# POWER_NODE.net
KiCad netlist of a schematic drawn in Altium Designer
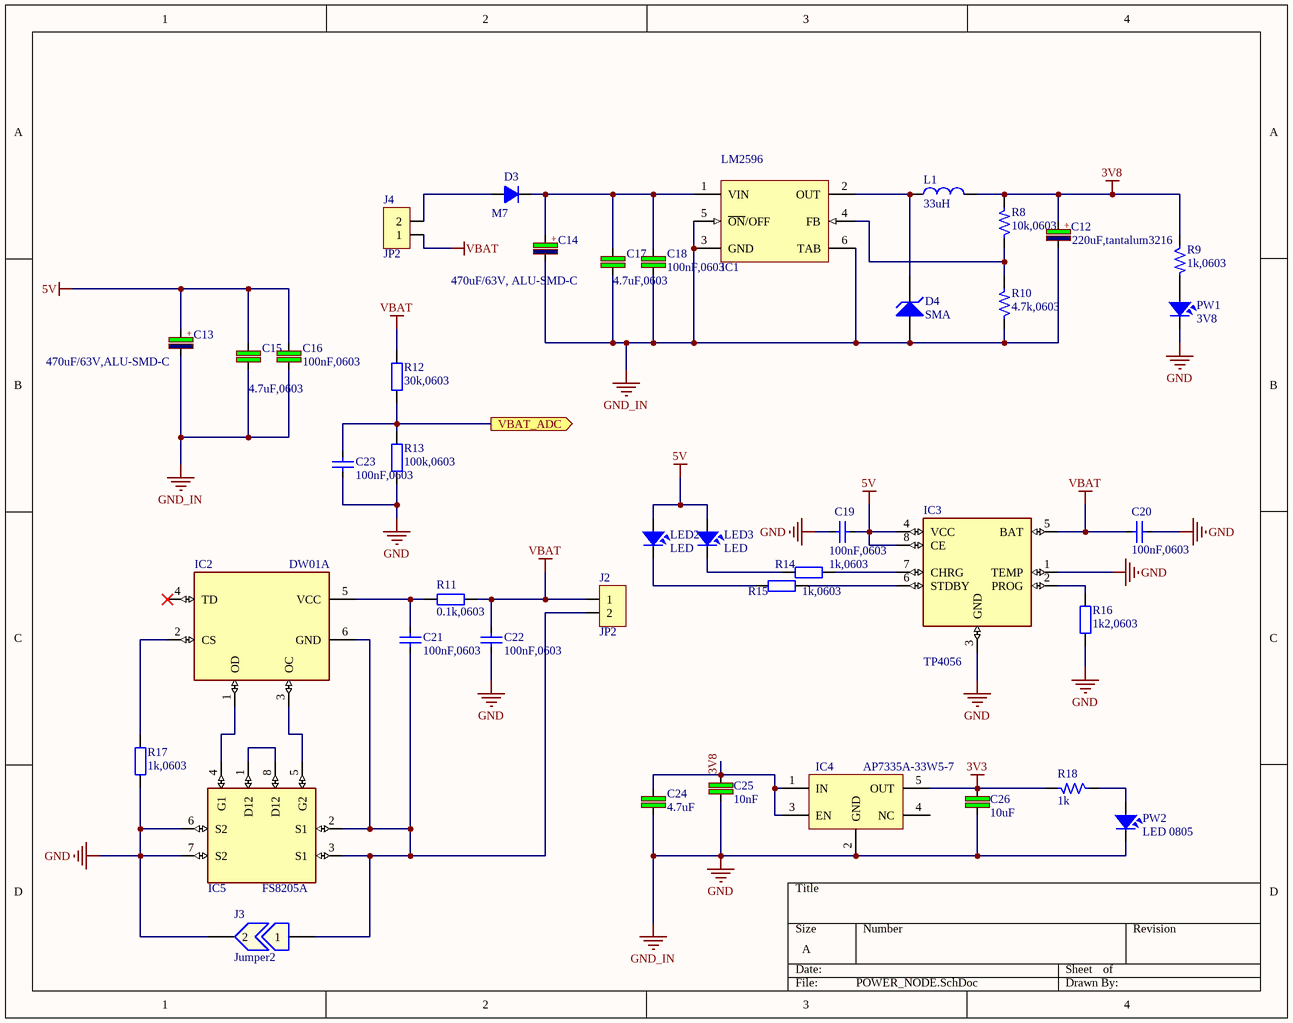
[diagram p0: POWER_NODE.SchDoc]

(export (version "E")
  (design (tool "Eeschema 10.0.6"))
  (components
    (comp (ref "C12")
      (value "220uF,tantalum3216")
      (footprint "CAP_TANTALUM_3216")
      (description "220µF Molded Tantalum Polymer Capacitor 16V 2917 (7343 Metric) 40mOhm @ 100kHz")
      (fields
        (field (name "MANUFACTURER") "AVX Corporation")
        (field (name "PART NUMBER") "TCME227M016R0040E")
      )
      (libsource (lib "Anh_Trung") (part "CP5"))
    )
    (comp (ref "C13")
      (value "470uF/63V,ALU-SMD-C")
      (footprint "CAP-ALU-SMD-C")
      (description "Cap 470uF/63V")
      (libsource (lib "Main") (part "CP3"))
    )
    (comp (ref "C14")
      (value "470uF/63V, ALU-SMD-C")
      (footprint "CAP-ALU-SMD-C")
      (description "Cap 470uF/63V")
      (libsource (lib "Main") (part "CP3"))
    )
    (comp (ref "C15")
      (value "4.7uF,0603")
      (footprint "CAP_0603")
      (description "4.7µF ±10% 35V Ceramic Capacitor X5R 0805 (2012 Metric)")
      (fields
        (field (name "MANUFACTURER") "Samsung Electro-Mechanics")
        (field (name "PART NUMBER") "CL21A475KLCLQNC")
      )
      (libsource (lib "Anh_Trung") (part "C"))
    )
    (comp (ref "C16")
      (value "100nF,0603")
      (footprint "CAP_0603")
      (description "4.7µF ±10% 35V Ceramic Capacitor X5R 0805 (2012 Metric)")
      (fields
        (field (name "MANUFACTURER") "Samsung Electro-Mechanics")
        (field (name "PART NUMBER") "CL21A475KLCLQNC")
      )
      (libsource (lib "Anh_Trung") (part "C"))
    )
    (comp (ref "C17")
      (value "4.7uF,0603")
      (footprint "CAP_0603")
      (description "4.7µF ±10% 35V Ceramic Capacitor X5R 0805 (2012 Metric)")
      (fields
        (field (name "MANUFACTURER") "Samsung Electro-Mechanics")
        (field (name "PART NUMBER") "CL21A475KLCLQNC")
      )
      (libsource (lib "Anh_Trung") (part "C"))
    )
    (comp (ref "C18")
      (value "100nF,0603")
      (footprint "CAP_0603")
      (description "4.7µF ±10% 35V Ceramic Capacitor X5R 0805 (2012 Metric)")
      (fields
        (field (name "MANUFACTURER") "Samsung Electro-Mechanics")
        (field (name "PART NUMBER") "CL21A475KLCLQNC")
      )
      (libsource (lib "Anh_Trung") (part "C"))
    )
    (comp (ref "C19")
      (value "100nF,0603")
      (footprint "CAP_0603")
      (description "Capacitor")
      (fields (field (name "PUBLISHER") "Altium Limited"))
      (libsource (lib "My Library") (part "CapSMD"))
    )
    (comp (ref "C20")
      (value "100nF,0603")
      (footprint "CAP_0603")
      (description "Capacitor")
      (fields (field (name "PUBLISHER") "Altium Limited"))
      (libsource (lib "My Library") (part "CapSMD"))
    )
    (comp (ref "C21")
      (value "100nF,0603")
      (footprint "CAP_0603")
      (description "Capacitor")
      (fields (field (name "PUBLISHER") "Altium Limited"))
      (libsource (lib "My Library") (part "CapSMD"))
    )
    (comp (ref "C22")
      (value "100nF,0603")
      (footprint "CAP_0603")
      (description "Capacitor")
      (fields (field (name "PUBLISHER") "Altium Limited"))
      (libsource (lib "My Library") (part "CapSMD"))
    )
    (comp (ref "C23")
      (value "100nF,0603")
      (footprint "CAP_0603")
      (description "Capacitor")
      (fields (field (name "PUBLISHER") "Altium Limited"))
      (libsource (lib "My Library") (part "CapSMD"))
    )
    (comp (ref "C24")
      (value "4.7uF")
      (footprint "CAP_0603")
      (description "4.7µF ±10% 35V Ceramic Capacitor X5R 0805 (2012 Metric)")
      (fields
        (field (name "MANUFACTURER") "Samsung Electro-Mechanics")
        (field (name "PART NUMBER") "CL21A475KLCLQNC")
      )
      (libsource (lib "Anh_Trung") (part "C"))
    )
    (comp (ref "C25")
      (value "10nF")
      (footprint "CAP_0603")
      (description "Cap SMD")
      (fields
        (field (name "MANUFACTURER") "Samsung Electro-Mechanics")
        (field (name "PART NUMBER") "CL21A106KPFNNNG")
      )
      (libsource (lib "") (part "C_1"))
    )
    (comp (ref "C26")
      (value "10uF")
      (footprint "CAP_0603")
      (description "Cap SMD")
      (fields
        (field (name "MANUFACTURER") "Samsung Electro-Mechanics")
        (field (name "PART NUMBER") "CL21A106KPFNNNG")
      )
      (libsource (lib "") (part "C_1"))
    )
    (comp (ref "D3")
      (value "M7")
      (footprint "SMA")
      (description "Diode 1A")
      (libsource (lib "Main") (part "D1A"))
    )
    (comp (ref "D4")
      (value "SMA")
      (footprint "SMA")
      (description "Zener Diode")
      (fields (field (name "PUBLISHER") "Altium Limited"))
      (libsource (lib "My Library 2") (part "Diode Zener"))
    )
    (comp (ref "IC1")
      (value "LM2596")
      (footprint "TO-263")
      (description "LM2576")
      (libsource (lib "Main") (part "LM2576"))
    )
    (comp (ref "IC2")
      (value "DW01A")
      (footprint "SOT23-6")
      (description "One Cell Lithium-ion/Polymer Battery Protection IC")
      (libsource (lib "My Library") (part "DW01A"))
    )
    (comp (ref "IC3")
      (value "TP4056")
      (footprint "TP4056")
      (description "Complete single cell Li-Ion battery with a constant current / constant voltage linear charger")
      (libsource (lib "My Library") (part "TP4056"))
    )
    (comp (ref "IC4")
      (value "AP7335A-33W5-7")
      (footprint "SOT23-5")
      (libsource (lib "Anh_Trung") (part "AP7335A-33W5-7"))
    )
    (comp (ref "IC5") (value "FS8205A") (footprint "FS8205A") (libsource (lib "My Library") (part "FS8205A")))
    (comp (ref "J2")
      (value "JP2")
      (footprint "KF2-5.08")
      (description "WR-PHD 2.54 mm Angled Socket Header")
      (fields
        (field (name "MANUFACTURER") "Würth Elektronik eiSos GmbH")
        (field (name "PARTNO") "613002143121")
        (field (name "CREATED BY") "Karrer Zheng")
      )
      (libsource (lib "") (part "JP2_1"))
    )
    (comp (ref "J3")
      (value "Jumper2")
      (footprint "JUMPER2")
      (description "Jumper, 2-Pin")
      (libsource (lib "My Library") (part "Jumper2"))
    )
    (comp (ref "J4")
      (value "JP2")
      (footprint "KF2-5.08")
      (description "WR-PHD 2.54 mm Angled Socket Header")
      (fields
        (field (name "MANUFACTURER") "Würth Elektronik eiSos GmbH")
        (field (name "PARTNO") "613002143121")
        (field (name "CREATED BY") "Karrer Zheng")
      )
      (libsource (lib "My Library") (part "JP2"))
    )
    (comp (ref "L1")
      (value "33uH")
      (footprint "Inductor_SMD")
      (description "22µH Shielded Inductor 1.65A 96mOhm Max Nonstandard")
      (fields (field (name "MANUFACTURER") "Bourns Inc.") (field (name "PART NUMBER") "SRR0745A-220M"))
      (libsource (lib "Main") (part "L1"))
    )
    (comp (ref "LED2")
      (value "LED")
      (footprint "LED-0805-Blue")
      (description "LED Single colour Green and Red")
      (libsource (lib "My Library") (part "LED"))
    )
    (comp (ref "LED3")
      (value "LED")
      (footprint "LED-0805-Blue")
      (description "LED Single colour Green and Red")
      (libsource (lib "My Library") (part "LED"))
    )
    (comp (ref "PW1")
      (value "3V8")
      (footprint "LED-0805-Blue")
      (description "LED RED DIFFUSED 0805 SMD")
      (fields
        (field (name "MANUFACTURER") "OSRAM Opto Semiconductors Inc.")
        (field (name "PART NUMBER") "LS R976-NR-1")
      )
      (libsource (lib "Anh_Trung") (part "LED"))
    )
    (comp (ref "PW2")
      (value "LED 0805")
      (footprint "LED-0805-Blue")
      (description "LED RED DIFFUSED 0805 SMD")
      (fields
        (field (name "MANUFACTURER") "OSRAM Opto Semiconductors Inc.")
        (field (name "PART NUMBER") "LS R976-NR-1")
      )
      (libsource (lib "Main") (part "LED"))
    )
    (comp (ref "R8")
      (value "10k,0603")
      (footprint "RES-SMD-0603")
      (description "RES SMD 10K OHM 1% 1/8W 0805")
      (fields (field (name "MANUFACTURER") "Yageo") (field (name "PART NUMBER") "RC0805FR-0710KL"))
      (libsource (lib "Anh_Trung") (part "R"))
    )
    (comp (ref "R9")
      (value "1k,0603")
      (footprint "RES-SMD-0603")
      (description "Resistor 1/4W")
      (fields (field (name "MANUFACTURER") "Yageo") (field (name "PART NUMBER") "RC0805FR-071KL"))
      (libsource (lib "Anh_Trung") (part "R"))
    )
    (comp (ref "R10")
      (value "4.7k,0603")
      (footprint "RES-SMD-0603")
      (description "RES SMD 3.3K OHM 1% 1/8W 0805")
      (fields (field (name "MANUFACTURER") "Yageo") (field (name "PART NUMBER") "RC0805FR-073K3L"))
      (libsource (lib "Anh_Trung") (part "R"))
    )
    (comp (ref "R11")
      (value "0.1k,0603")
      (footprint "RES-SMD-0603")
      (description "Resistor SMD")
      (fields
        (field (name "MANUFACTURER") "Generic Components")
        (field (name "PUBLISHER") "Altium Hobart Technology Centre")
      )
      (libsource (lib "My Library") (part "Resistor - SMD"))
    )
    (comp (ref "R12")
      (value "30k,0603")
      (footprint "RES-SMD-0603")
      (description "Resistor SMD")
      (fields
        (field (name "MANUFACTURER") "Generic Components")
        (field (name "PUBLISHER") "Altium Hobart Technology Centre")
      )
      (libsource (lib "My Library") (part "Resistor - SMD"))
    )
    (comp (ref "R13")
      (value "100k,0603")
      (footprint "RES-SMD-0603")
      (description "Resistor SMD")
      (fields
        (field (name "MANUFACTURER") "Generic Components")
        (field (name "PUBLISHER") "Altium Hobart Technology Centre")
      )
      (libsource (lib "My Library") (part "Resistor - SMD"))
    )
    (comp (ref "R14")
      (value "1k,0603")
      (footprint "RES-SMD-0603")
      (description "Resistor SMD")
      (fields
        (field (name "MANUFACTURER") "Generic Components")
        (field (name "PUBLISHER") "Altium Hobart Technology Centre")
      )
      (libsource (lib "My Library") (part "Resistor - SMD"))
    )
    (comp (ref "R15")
      (value "1k,0603")
      (footprint "RES-SMD-0603")
      (description "Resistor SMD")
      (fields
        (field (name "MANUFACTURER") "Generic Components")
        (field (name "PUBLISHER") "Altium Hobart Technology Centre")
      )
      (libsource (lib "My Library") (part "Resistor - SMD"))
    )
    (comp (ref "R16")
      (value "1k2,0603")
      (footprint "RES-SMD-0603")
      (description "Resistor SMD")
      (fields
        (field (name "MANUFACTURER") "Generic Components")
        (field (name "PUBLISHER") "Altium Hobart Technology Centre")
      )
      (libsource (lib "My Library") (part "Resistor - SMD"))
    )
    (comp (ref "R17")
      (value "1k,0603")
      (footprint "RES-SMD-0603")
      (description "Resistor SMD")
      (fields
        (field (name "MANUFACTURER") "Generic Components")
        (field (name "PUBLISHER") "Altium Hobart Technology Centre")
      )
      (libsource (lib "My Library") (part "Resistor - SMD"))
    )
    (comp (ref "R18")
      (value "1k")
      (footprint "RES-SMD-0603")
      (description "Resistor 1/4W")
      (fields (field (name "MANUFACTURER") "Yageo") (field (name "PART NUMBER") "RC0805FR-071KL"))
      (libsource (lib "Anh_Trung") (part "R"))
    )
  )
  (nets
    (net (code "1") (name "/VBAT_ADC") (class "Default")
      (node (ref "C23") (pin "2") (pinfunction "2_2") (pintype "passive"))
      (node (ref "R12") (pin "1") (pinfunction "1_1") (pintype "passive"))
      (node (ref "R13") (pin "2") (pinfunction "2_2") (pintype "passive"))
    )
    (net (code "2") (name "3V3") (class "Default")
      (node (ref "C26") (pin "1") (pinfunction "1_1") (pintype "passive"))
      (node (ref "IC4") (pin "5") (pinfunction "OUT_5") (pintype "passive"))
      (node (ref "R18") (pin "2") (pinfunction "2_2") (pintype "passive"))
    )
    (net (code "3") (name "3V8") (class "Default")
      (node (ref "C12") (pin "1") (pinfunction "1_1") (pintype "passive"))
      (node (ref "C24") (pin "2") (pinfunction "2_2") (pintype "passive"))
      (node (ref "C25") (pin "1") (pinfunction "1_1") (pintype "passive"))
      (node (ref "IC4") (pin "1") (pinfunction "IN_1") (pintype "passive"))
      (node (ref "IC4") (pin "3") (pinfunction "EN_3") (pintype "passive"))
      (node (ref "L1") (pin "2") (pinfunction "2_2") (pintype "passive"))
      (node (ref "R8") (pin "2") (pinfunction "2_2") (pintype "passive"))
      (node (ref "R9") (pin "1") (pinfunction "1_1") (pintype "passive"))
    )
    (net (code "4") (name "5V") (class "Default")
      (node (ref "C13") (pin "1") (pinfunction "1_1") (pintype "passive"))
      (node (ref "C15") (pin "2") (pinfunction "2_2") (pintype "passive"))
      (node (ref "C16") (pin "2") (pinfunction "2_2") (pintype "passive"))
      (node (ref "C19") (pin "1") (pinfunction "1_1") (pintype "passive"))
      (node (ref "IC3") (pin "4") (pinfunction "VCC_4") (pintype "bidirectional"))
      (node (ref "IC3") (pin "8") (pinfunction "CE_8") (pintype "bidirectional"))
      (node (ref "LED2") (pin "1") (pinfunction "1_1") (pintype "passive"))
      (node (ref "LED3") (pin "1") (pinfunction "1_1") (pintype "passive"))
    )
    (net (code "5") (name "GND") (class "Default")
      (node (ref "C12") (pin "2") (pinfunction "2_2") (pintype "passive"))
      (node (ref "C13") (pin "2") (pinfunction "2_2") (pintype "passive"))
      (node (ref "C14") (pin "2") (pinfunction "2_2") (pintype "passive"))
      (node (ref "C15") (pin "1") (pinfunction "1_1") (pintype "passive"))
      (node (ref "C16") (pin "1") (pinfunction "1_1") (pintype "passive"))
      (node (ref "C17") (pin "1") (pinfunction "1_1") (pintype "passive"))
      (node (ref "C18") (pin "1") (pinfunction "1_1") (pintype "passive"))
      (node (ref "C19") (pin "2") (pinfunction "2_2") (pintype "passive"))
      (node (ref "C20") (pin "1") (pinfunction "1_1") (pintype "passive"))
      (node (ref "C22") (pin "1") (pinfunction "1_1") (pintype "passive"))
      (node (ref "C23") (pin "1") (pinfunction "1_1") (pintype "passive"))
      (node (ref "C24") (pin "1") (pinfunction "1_1") (pintype "passive"))
      (node (ref "C25") (pin "2") (pinfunction "2_2") (pintype "passive"))
      (node (ref "C26") (pin "2") (pinfunction "2_2") (pintype "passive"))
      (node (ref "D4") (pin "1") (pinfunction "A_1") (pintype "passive"))
      (node (ref "IC1") (pin "3") (pinfunction "GND_3") (pintype "power_in"))
      (node (ref "IC1") (pin "5") (pinfunction "~{ON}/OFF_5") (pintype "input"))
      (node (ref "IC1") (pin "6") (pinfunction "TAB_6") (pintype "power_in"))
      (node (ref "IC3") (pin "1") (pinfunction "TEMP_1") (pintype "bidirectional"))
      (node (ref "IC3") (pin "3") (pinfunction "GND_3") (pintype "bidirectional"))
      (node (ref "IC4") (pin "2") (pinfunction "GND_2") (pintype "passive"))
      (node (ref "IC5") (pin "6") (pinfunction "S2_6") (pintype "bidirectional"))
      (node (ref "IC5") (pin "7") (pinfunction "S2_7") (pintype "bidirectional"))
      (node (ref "J3") (pin "2") (pinfunction "2_2") (pintype "passive"))
      (node (ref "PW1") (pin "2") (pinfunction "2_2") (pintype "passive"))
      (node (ref "PW2") (pin "2") (pinfunction "2_2") (pintype "passive"))
      (node (ref "R10") (pin "1") (pinfunction "1_1") (pintype "passive"))
      (node (ref "R13") (pin "1") (pinfunction "1_1") (pintype "passive"))
      (node (ref "R16") (pin "2") (pinfunction "2_2") (pintype "passive"))
      (node (ref "R17") (pin "2") (pinfunction "2_2") (pintype "passive"))
    )
    (net (code "6") (name "Net-(D3-A)") (class "Default")
      (node (ref "D3") (pin "1") (pinfunction "A_1") (pintype "passive"))
      (node (ref "J4") (pin "2") (pinfunction "2_2") (pintype "passive"))
    )
    (net (code "7") (name "Net-(D3-K)") (class "Default")
      (node (ref "C14") (pin "1") (pinfunction "1_1") (pintype "passive"))
      (node (ref "C17") (pin "2") (pinfunction "2_2") (pintype "passive"))
      (node (ref "C18") (pin "2") (pinfunction "2_2") (pintype "passive"))
      (node (ref "D3") (pin "2") (pinfunction "K_2") (pintype "passive"))
      (node (ref "IC1") (pin "1") (pinfunction "VIN_1") (pintype "power_in"))
    )
    (net (code "8") (name "Net-(D4-K)") (class "Default")
      (node (ref "D4") (pin "2") (pinfunction "K_2") (pintype "passive"))
      (node (ref "IC1") (pin "2") (pinfunction "OUT_2") (pintype "power_in"))
      (node (ref "L1") (pin "1") (pinfunction "1_1") (pintype "passive"))
    )
    (net (code "9") (name "Net-(IC1-FB)") (class "Default")
      (node (ref "IC1") (pin "4") (pinfunction "FB_4") (pintype "input"))
      (node (ref "R10") (pin "2") (pinfunction "2_2") (pintype "passive"))
      (node (ref "R8") (pin "1") (pinfunction "1_1") (pintype "passive"))
    )
    (net (code "10") (name "Net-(IC2-CS)") (class "Default")
      (node (ref "IC2") (pin "2") (pinfunction "CS_2") (pintype "bidirectional"))
      (node (ref "R17") (pin "1") (pinfunction "1_1") (pintype "passive"))
    )
    (net (code "11") (name "Net-(IC2-GND)") (class "Default")
      (node (ref "C21") (pin "1") (pinfunction "1_1") (pintype "passive"))
      (node (ref "IC2") (pin "6") (pinfunction "GND_6") (pintype "power_in"))
      (node (ref "IC5") (pin "2") (pinfunction "S1_2") (pintype "bidirectional"))
      (node (ref "IC5") (pin "3") (pinfunction "S1_3") (pintype "bidirectional"))
      (node (ref "J2") (pin "2") (pinfunction "2_2") (pintype "passive"))
      (node (ref "J3") (pin "1") (pinfunction "1_1") (pintype "passive"))
    )
    (net (code "12") (name "Net-(IC2-OC)") (class "Default")
      (node (ref "IC2") (pin "3") (pinfunction "OC_3") (pintype "bidirectional"))
      (node (ref "IC5") (pin "5") (pinfunction "G2_5") (pintype "bidirectional"))
    )
    (net (code "13") (name "Net-(IC2-OD)") (class "Default")
      (node (ref "IC2") (pin "1") (pinfunction "OD_1") (pintype "bidirectional"))
      (node (ref "IC5") (pin "4") (pinfunction "G1_4") (pintype "bidirectional"))
    )
    (net (code "14") (name "Net-(IC2-VCC)") (class "Default")
      (node (ref "C21") (pin "2") (pinfunction "2_2") (pintype "passive"))
      (node (ref "IC2") (pin "5") (pinfunction "VCC_5") (pintype "power_in"))
      (node (ref "R11") (pin "1") (pinfunction "1_1") (pintype "passive"))
    )
    (net (code "15") (name "Net-(IC3-CHRG)") (class "Default")
      (node (ref "IC3") (pin "7") (pinfunction "CHRG_7") (pintype "bidirectional"))
      (node (ref "R14") (pin "2") (pinfunction "2_2") (pintype "passive"))
    )
    (net (code "16") (name "Net-(IC3-PROG)") (class "Default")
      (node (ref "IC3") (pin "2") (pinfunction "PROG_2") (pintype "bidirectional"))
      (node (ref "R16") (pin "1") (pinfunction "1_1") (pintype "passive"))
    )
    (net (code "17") (name "Net-(IC3-STDBY)") (class "Default")
      (node (ref "IC3") (pin "6") (pinfunction "STDBY_6") (pintype "bidirectional"))
      (node (ref "R15") (pin "2") (pinfunction "2_2") (pintype "passive"))
    )
    (net (code "18") (name "Net-(IC5-D12-Pad1)") (class "Default")
      (node (ref "IC5") (pin "1") (pinfunction "D12_1") (pintype "bidirectional"))
      (node (ref "IC5") (pin "8") (pinfunction "D12_8") (pintype "bidirectional"))
    )
    (net (code "19") (name "Net-(LED2-Pad2)") (class "Default")
      (node (ref "LED2") (pin "2") (pinfunction "2_2") (pintype "passive"))
      (node (ref "R15") (pin "1") (pinfunction "1_1") (pintype "passive"))
    )
    (net (code "20") (name "Net-(LED3-Pad2)") (class "Default")
      (node (ref "LED3") (pin "2") (pinfunction "2_2") (pintype "passive"))
      (node (ref "R14") (pin "1") (pinfunction "1_1") (pintype "passive"))
    )
    (net (code "21") (name "Net-(PW1-Pad1)") (class "Default")
      (node (ref "PW1") (pin "1") (pinfunction "1_1") (pintype "passive"))
      (node (ref "R9") (pin "2") (pinfunction "2_2") (pintype "passive"))
    )
    (net (code "22") (name "Net-(PW2-Pad1)") (class "Default")
      (node (ref "PW2") (pin "1") (pinfunction "1_1") (pintype "passive"))
      (node (ref "R18") (pin "1") (pinfunction "1_1") (pintype "passive"))
    )
    (net (code "23") (name "VBAT") (class "Default")
      (node (ref "C20") (pin "2") (pinfunction "2_2") (pintype "passive"))
      (node (ref "C22") (pin "2") (pinfunction "2_2") (pintype "passive"))
      (node (ref "IC3") (pin "5") (pinfunction "BAT_5") (pintype "bidirectional"))
      (node (ref "J2") (pin "1") (pinfunction "1_1") (pintype "passive"))
      (node (ref "J4") (pin "1") (pinfunction "1_1") (pintype "passive"))
      (node (ref "R11") (pin "2") (pinfunction "2_2") (pintype "passive"))
      (node (ref "R12") (pin "2") (pinfunction "2_2") (pintype "passive"))
    )
    (net (code "24") (name "unconnected-(IC2-TD-Pad4)") (class "Default")
      (node (ref "IC2") (pin "4") (pinfunction "TD_4") (pintype "bidirectional+no_connect"))
    )
    (net (code "25") (name "unconnected-(IC4-NC-Pad4)") (class "Default")
      (node (ref "IC4") (pin "4") (pinfunction "NC_4") (pintype "passive"))
    )
  )
)
